# TK105_Hodetelefonforsterker.net
KiCad netlist of a schematic drawn in Altium Designer
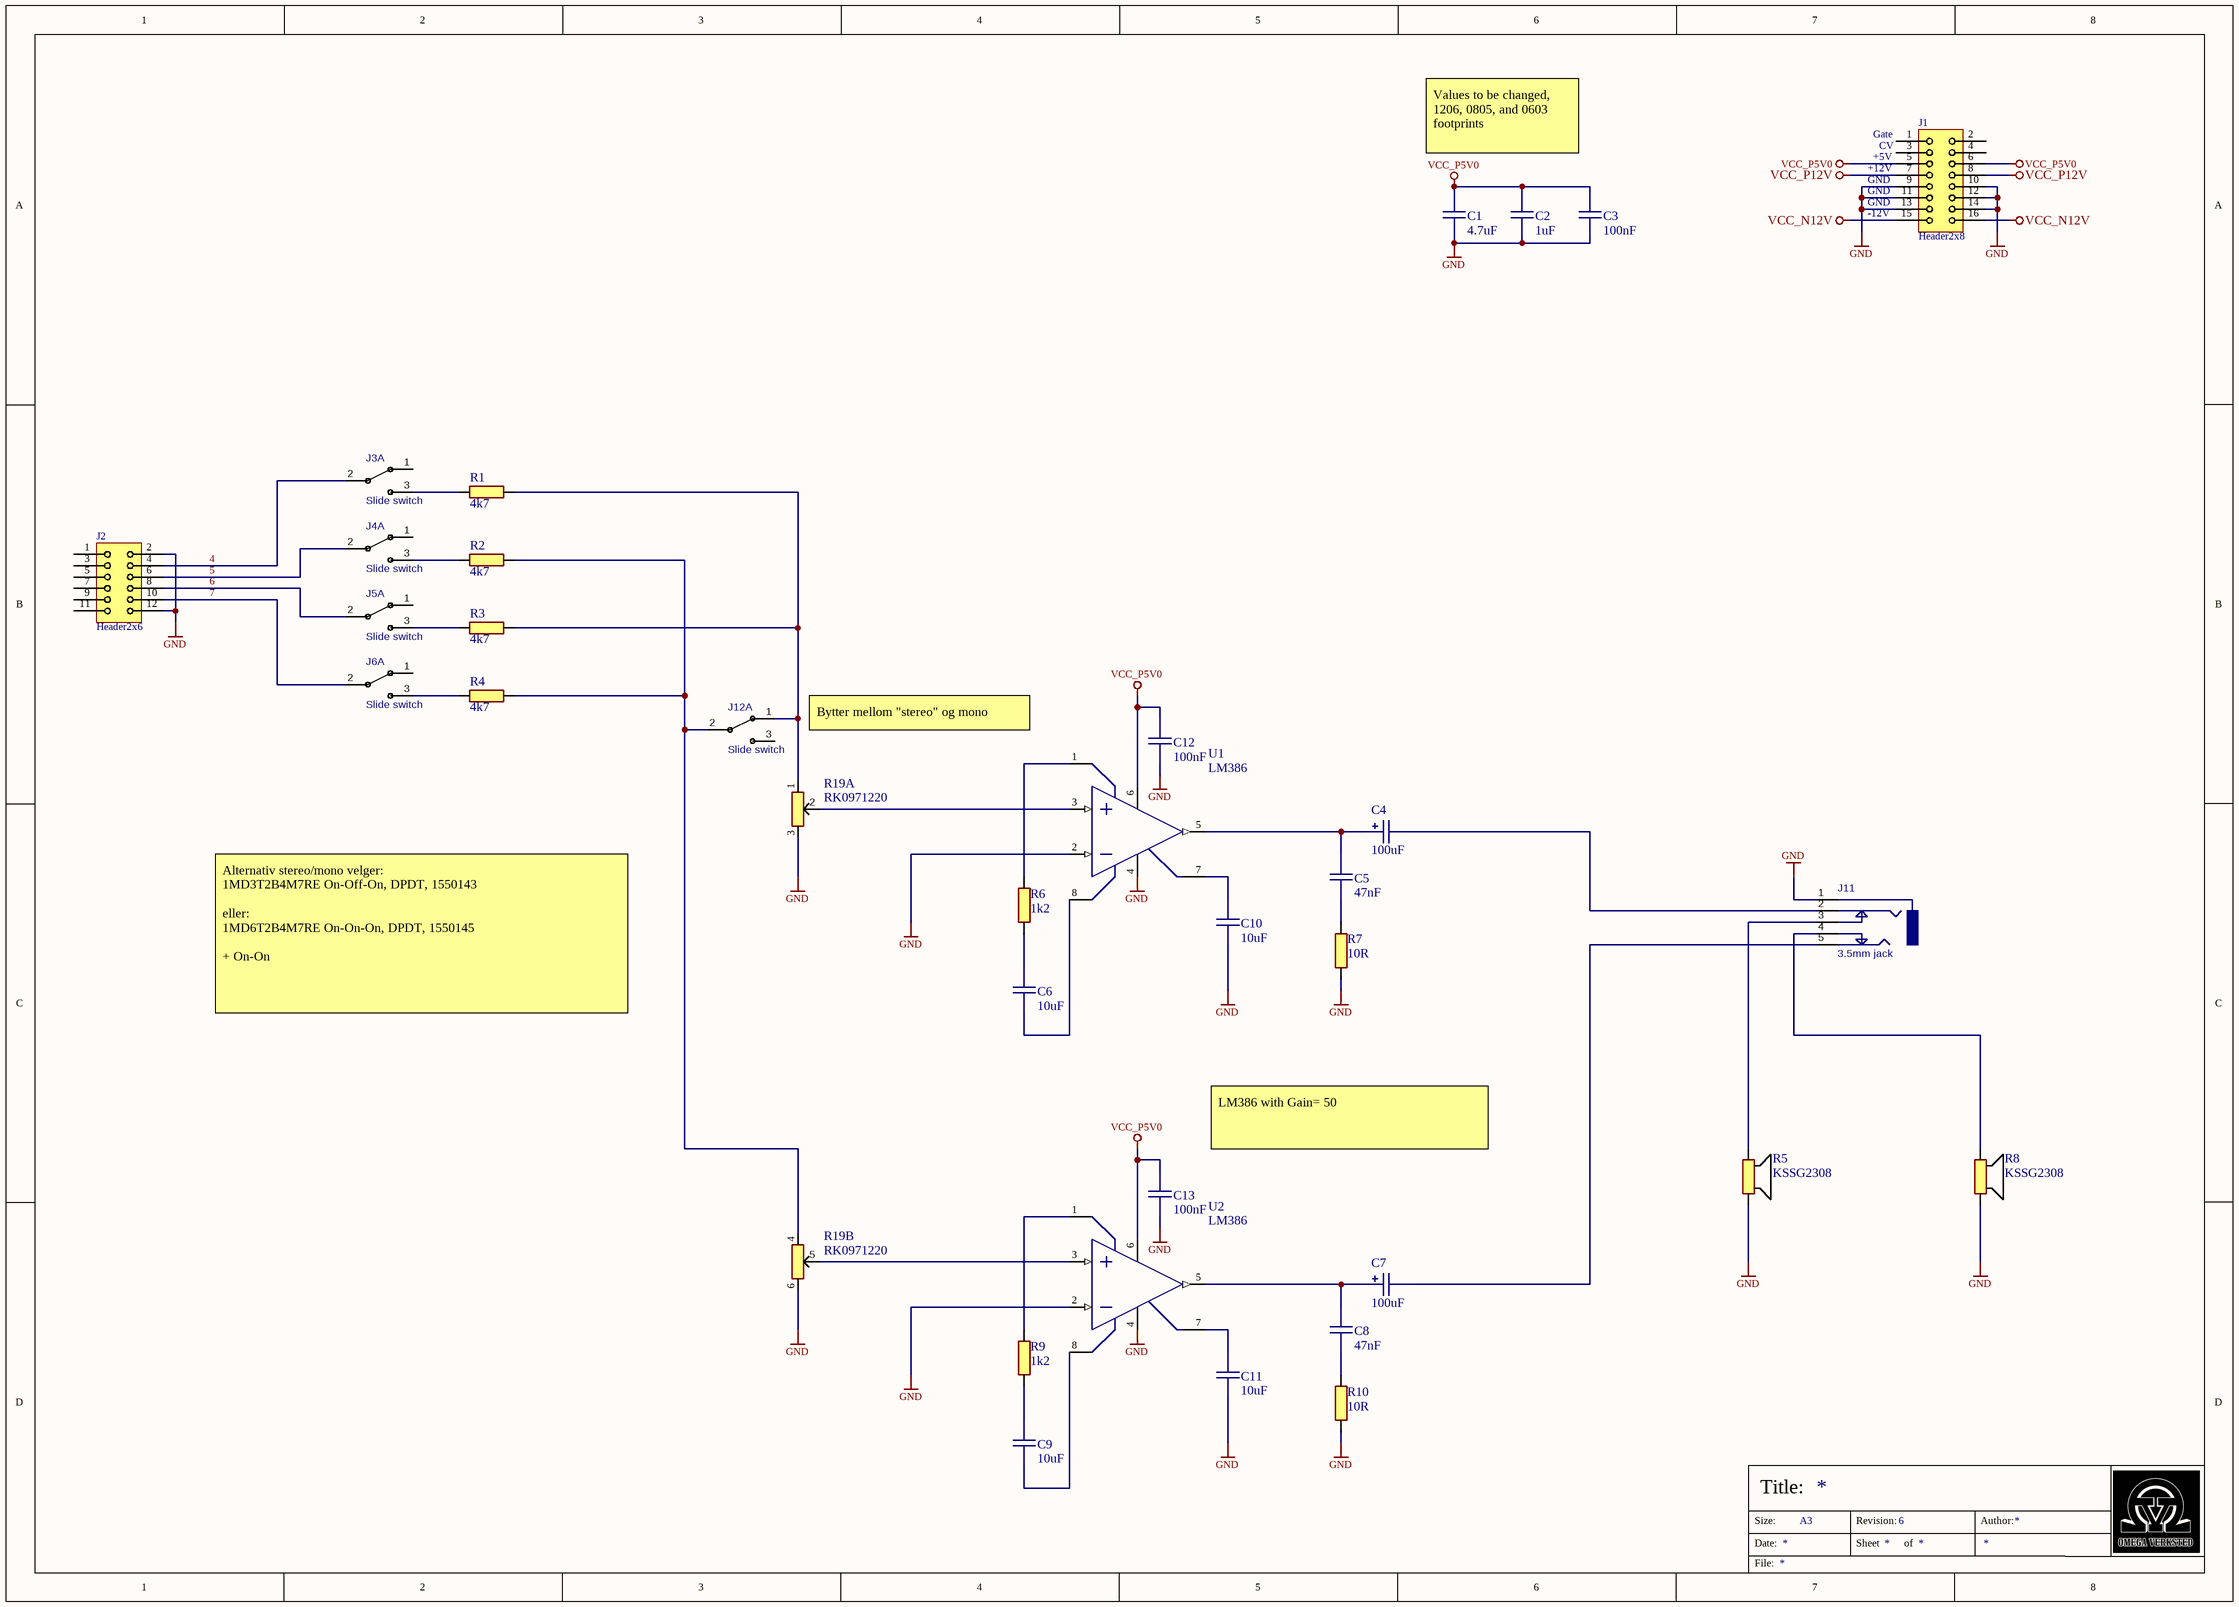
[diagram p0: TK105_Hodetelefonforsterker.SchDoc]

(export (version "E")
  (design (tool "Eeschema 10.0.6"))
  (components
    (comp (ref "C1")
      (value "4.7uF")
      (footprint "CAPC1206(3216)170_N")
      (description "X7R 50V")
      (libsource (lib "OVLib") (part "CAP"))
    )
    (comp (ref "C2")
      (value "1uF")
      (footprint "CAPC0805(2012)100_N")
      (description "X7R 50V 10%")
      (libsource (lib "OVLib") (part "CAP"))
    )
    (comp (ref "C3")
      (value "100nF")
      (footprint "CAPC0603(1608)55_N")
      (description "X7R 50V 5%")
      (libsource (lib "OVLib") (part "CAP"))
    )
    (comp (ref "C4")
      (value "100uF")
      (footprint "CAPPR25D06H11")
      (description "25V 2.5mm pitch")
      (libsource (lib "OVLib_64") (part "POLCAP"))
    )
    (comp (ref "C5")
      (value "47nF")
      (footprint "CAPC0603(1608)55_N")
      (description "X7R 50V 5%")
      (libsource (lib "OVLib_64") (part "CAP"))
    )
    (comp (ref "C6")
      (value "10uF")
      (footprint "CAPC0805(2012)100_N")
      (description "X5R 6.3V 10%")
      (libsource (lib "OVLib_64") (part "CAP"))
    )
    (comp (ref "C7")
      (value "100uF")
      (footprint "CAPPR25D06H11")
      (description "25V 2.5mm pitch")
      (libsource (lib "OVLib_64") (part "POLCAP"))
    )
    (comp (ref "C8")
      (value "47nF")
      (footprint "CAPC0603(1608)55_N")
      (description "X7R 50V 5%")
      (libsource (lib "OVLib_64") (part "CAP"))
    )
    (comp (ref "C9")
      (value "10uF")
      (footprint "CAPC0805(2012)100_N")
      (description "X5R 6.3V 10%")
      (libsource (lib "OVLib_64") (part "CAP"))
    )
    (comp (ref "C10")
      (value "10uF")
      (footprint "CAPC0805(2012)100_N")
      (description "X5R 6.3V 10%")
      (libsource (lib "OVLib_64") (part "CAP"))
    )
    (comp (ref "C11")
      (value "10uF")
      (footprint "CAPC0805(2012)100_N")
      (description "X5R 6.3V 10%")
      (libsource (lib "OVLib_64") (part "CAP"))
    )
    (comp (ref "C12")
      (value "100nF")
      (footprint "CAPC0603(1608)55_N")
      (description "X7R 50V 5%")
      (libsource (lib "OVLib_64") (part "CAP"))
    )
    (comp (ref "C13")
      (value "100nF")
      (footprint "CAPC0603(1608)55_N")
      (description "X7R 50V 5%")
      (libsource (lib "OVLib_64") (part "CAP"))
    )
    (comp (ref "J1")
      (value "Header2x8")
      (footprint "HDRV16W64P254_2X8_Shrouded")
      (libsource (lib "OVLib_64") (part "Header2x8"))
    )
    (comp (ref "J2")
      (value "Header2x6")
      (footprint "HDRV12W64P254_2X6_RA")
      (description "Header")
      (libsource (lib "OVLib_64") (part "Header2x6"))
    )
    (comp (ref "J3")
      (value "Slide switch")
      (footprint "1MS1T2B4M7RE")
      (description "Toggle Switch SPDT On-On")
      (libsource (lib "OVLib_64") (part "Slide_switch_DPDT_RA"))
    )
    (comp (ref "J4")
      (value "Slide switch")
      (footprint "1MS1T2B4M7RE")
      (description "Toggle Switch SPDT On-On")
      (libsource (lib "OVLib_64") (part "Slide_switch_DPDT_RA"))
    )
    (comp (ref "J5")
      (value "Slide switch")
      (footprint "1MS1T2B4M7RE")
      (description "Toggle Switch SPDT On-On")
      (libsource (lib "OVLib_64") (part "Slide_switch_DPDT_RA"))
    )
    (comp (ref "J6")
      (value "Slide switch")
      (footprint "1MS1T2B4M7RE")
      (description "Toggle Switch SPDT On-On")
      (libsource (lib "OVLib_64") (part "Slide_switch_DPDT_RA"))
    )
    (comp (ref "J11")
      (value "3.5mm jack")
      (footprint "PJ-306M")
      (description "PCB panel mount PJ-306M")
      (libsource (lib "OVLib_64") (part "3.5MM_JACK"))
    )
    (comp (ref "J12")
      (value "Slide switch")
      (footprint "1MS1T2B4M7RE")
      (description "Toggle Switch SPDT On-On")
      (libsource (lib "OVLib_64") (part "Slide_switch_DPDT_RA"))
    )
    (comp (ref "R1")
      (value "4k7")
      (footprint "RESC0603(1608)_N")
      (description "0.1W 1% Thick film resistor")
      (libsource (lib "") (part "Resistor2_1"))
    )
    (comp (ref "R2")
      (value "4k7")
      (footprint "RESC0603(1608)_N")
      (description "0.1W 1% Thick film resistor")
      (libsource (lib "") (part "Resistor2_1"))
    )
    (comp (ref "R3")
      (value "4k7")
      (footprint "RESC0603(1608)_N")
      (description "0.1W 1% Thick film resistor")
      (libsource (lib "") (part "Resistor2_1"))
    )
    (comp (ref "R4")
      (value "4k7")
      (footprint "RESC0603(1608)_N")
      (description "0.1W 1% Thick film resistor")
      (libsource (lib "") (part "Resistor2_1"))
    )
    (comp (ref "R5")
      (value "KSSG2308")
      (footprint "KSSG2308")
      (description "Speaker, Micro, 150 mW, 8 ohm, 1.5 kHz to 6 kHz")
      (libsource (lib "OVLib_64") (part "Speaker"))
    )
    (comp (ref "R6")
      (value "1k2")
      (footprint "RESC0603(1608)_N")
      (description "0.1W 1% Thick film resistor")
      (libsource (lib "OVLib_64") (part "Resistor2"))
    )
    (comp (ref "R7")
      (value "10R")
      (footprint "RESC0603(1608)_N")
      (description "0.1W 1% Thick film resistor")
      (libsource (lib "OVLib_64") (part "Resistor2"))
    )
    (comp (ref "R8")
      (value "KSSG2308")
      (footprint "KSSG2308")
      (description "Speaker, Micro, 150 mW, 8 ohm, 1.5 kHz to 6 kHz")
      (libsource (lib "OVLib_64") (part "Speaker"))
    )
    (comp (ref "R9")
      (value "1k2")
      (footprint "RESC0603(1608)_N")
      (description "0.1W 1% Thick film resistor")
      (libsource (lib "OVLib_64") (part "Resistor2"))
    )
    (comp (ref "R10")
      (value "10R")
      (footprint "RESC0603(1608)_N")
      (description "0.1W 1% Thick film resistor")
      (libsource (lib "OVLib_64") (part "Resistor2"))
    )
    (comp (ref "R19")
      (value "RK0971220")
      (footprint "RK0971220")
      (description "Stereo logarithmic potmeter")
      (libsource (lib "OVLib_64") (part "Stereo_Potmeter"))
    )
    (comp (ref "U1")
      (value "LM386")
      (footprint "SOIC127P590X363-8N")
      (description "Audio Power Amplifier, AB, 1 Channel, 4V to 12V, MSOP, 8 Pins")
      (libsource (lib "OVLib_64") (part "LM386"))
    )
    (comp (ref "U2")
      (value "LM386")
      (footprint "SOIC127P590X363-8N")
      (description "Audio Power Amplifier, AB, 1 Channel, 4V to 12V, MSOP, 8 Pins")
      (libsource (lib "OVLib_64") (part "LM386"))
    )
  )
  (nets
    (net (code "1") (name "/4") (class "Default")
      (node (ref "J2") (pin "4") (pinfunction "4_4") (pintype "passive"))
      (node (ref "J3") (pin "2") (pinfunction "2_2") (pintype "passive"))
    )
    (net (code "2") (name "/5") (class "Default")
      (node (ref "J2") (pin "6") (pinfunction "6_6") (pintype "passive"))
      (node (ref "J4") (pin "2") (pinfunction "2_2") (pintype "passive"))
    )
    (net (code "3") (name "/6") (class "Default")
      (node (ref "J2") (pin "8") (pinfunction "8_8") (pintype "passive"))
      (node (ref "J5") (pin "2") (pinfunction "2_2") (pintype "passive"))
    )
    (net (code "4") (name "/7") (class "Default")
      (node (ref "J2") (pin "10") (pinfunction "10_10") (pintype "passive"))
      (node (ref "J6") (pin "2") (pinfunction "2_2") (pintype "passive"))
    )
    (net (code "5") (name "GND") (class "Default")
      (node (ref "C1") (pin "1") (pinfunction "1_1") (pintype "passive"))
      (node (ref "C10") (pin "1") (pinfunction "1_1") (pintype "passive"))
      (node (ref "C11") (pin "1") (pinfunction "1_1") (pintype "passive"))
      (node (ref "C12") (pin "1") (pinfunction "1_1") (pintype "passive"))
      (node (ref "C13") (pin "1") (pinfunction "1_1") (pintype "passive"))
      (node (ref "C2") (pin "1") (pinfunction "1_1") (pintype "passive"))
      (node (ref "C3") (pin "1") (pinfunction "1_1") (pintype "passive"))
      (node (ref "J1") (pin "10") (pinfunction "10_10") (pintype "passive"))
      (node (ref "J1") (pin "11") (pinfunction "11_11") (pintype "passive"))
      (node (ref "J1") (pin "12") (pinfunction "12_12") (pintype "passive"))
      (node (ref "J1") (pin "13") (pinfunction "13_13") (pintype "passive"))
      (node (ref "J1") (pin "14") (pinfunction "14_14") (pintype "passive"))
      (node (ref "J1") (pin "9") (pinfunction "9_9") (pintype "passive"))
      (node (ref "J11") (pin "1") (pinfunction "1_1") (pintype "passive"))
      (node (ref "J2") (pin "12") (pinfunction "12_12") (pintype "passive"))
      (node (ref "J2") (pin "2") (pinfunction "2_2") (pintype "passive"))
      (node (ref "R10") (pin "1") (pinfunction "1_1") (pintype "passive"))
      (node (ref "R19") (pin "3") (pinfunction "3_3") (pintype "passive"))
      (node (ref "R19") (pin "6") (pinfunction "6_6") (pintype "passive"))
      (node (ref "R5") (pin "2") (pinfunction "2_2") (pintype "passive"))
      (node (ref "R7") (pin "1") (pinfunction "1_1") (pintype "passive"))
      (node (ref "R8") (pin "2") (pinfunction "2_2") (pintype "passive"))
      (node (ref "U1") (pin "2") (pinfunction "IN-_2") (pintype "input"))
      (node (ref "U1") (pin "4") (pinfunction "GND_4") (pintype "power_in"))
      (node (ref "U2") (pin "2") (pinfunction "IN-_2") (pintype "input"))
      (node (ref "U2") (pin "4") (pinfunction "GND_4") (pintype "power_in"))
    )
    (net (code "6") (name "Net-(C4-Pad1)") (class "Default")
      (node (ref "C4") (pin "1") (pinfunction "1_1") (pintype "passive"))
      (node (ref "J11") (pin "2") (pinfunction "2_2") (pintype "passive"))
    )
    (net (code "7") (name "Net-(C5-Pad1)") (class "Default")
      (node (ref "C5") (pin "1") (pinfunction "1_1") (pintype "passive"))
      (node (ref "R7") (pin "2") (pinfunction "2_2") (pintype "passive"))
    )
    (net (code "8") (name "Net-(C6-Pad1)") (class "Default")
      (node (ref "C6") (pin "1") (pinfunction "1_1") (pintype "passive"))
      (node (ref "U1") (pin "8") (pinfunction "GAIN_8") (pintype "passive"))
    )
    (net (code "9") (name "Net-(C6-Pad2)") (class "Default")
      (node (ref "C6") (pin "2") (pinfunction "2_2") (pintype "passive"))
      (node (ref "R6") (pin "1") (pinfunction "1_1") (pintype "passive"))
    )
    (net (code "10") (name "Net-(C7-Pad1)") (class "Default")
      (node (ref "C7") (pin "1") (pinfunction "1_1") (pintype "passive"))
      (node (ref "J11") (pin "5") (pinfunction "5_5") (pintype "passive"))
    )
    (net (code "11") (name "Net-(C8-Pad1)") (class "Default")
      (node (ref "C8") (pin "1") (pinfunction "1_1") (pintype "passive"))
      (node (ref "R10") (pin "2") (pinfunction "2_2") (pintype "passive"))
    )
    (net (code "12") (name "Net-(C9-Pad1)") (class "Default")
      (node (ref "C9") (pin "1") (pinfunction "1_1") (pintype "passive"))
      (node (ref "U2") (pin "8") (pinfunction "GAIN_8") (pintype "passive"))
    )
    (net (code "13") (name "Net-(C9-Pad2)") (class "Default")
      (node (ref "C9") (pin "2") (pinfunction "2_2") (pintype "passive"))
      (node (ref "R9") (pin "1") (pinfunction "1_1") (pintype "passive"))
    )
    (net (code "14") (name "Net-(J3-Pad3)") (class "Default")
      (node (ref "J3") (pin "3") (pinfunction "3_3") (pintype "passive"))
      (node (ref "R1") (pin "1") (pinfunction "1_1") (pintype "passive"))
    )
    (net (code "15") (name "Net-(J4-Pad3)") (class "Default")
      (node (ref "J4") (pin "3") (pinfunction "3_3") (pintype "passive"))
      (node (ref "R2") (pin "1") (pinfunction "1_1") (pintype "passive"))
    )
    (net (code "16") (name "Net-(J5-Pad3)") (class "Default")
      (node (ref "J5") (pin "3") (pinfunction "3_3") (pintype "passive"))
      (node (ref "R3") (pin "1") (pinfunction "1_1") (pintype "passive"))
    )
    (net (code "17") (name "Net-(J6-Pad3)") (class "Default")
      (node (ref "J6") (pin "3") (pinfunction "3_3") (pintype "passive"))
      (node (ref "R4") (pin "1") (pinfunction "1_1") (pintype "passive"))
    )
    (net (code "18") (name "Net-(J11-Pad3)") (class "Default")
      (node (ref "J11") (pin "3") (pinfunction "3_3") (pintype "passive"))
      (node (ref "R5") (pin "1") (pinfunction "1_1") (pintype "passive"))
    )
    (net (code "19") (name "Net-(J11-Pad4)") (class "Default")
      (node (ref "J11") (pin "4") (pinfunction "4_4") (pintype "passive"))
      (node (ref "R8") (pin "1") (pinfunction "1_1") (pintype "passive"))
    )
    (net (code "20") (name "Net-(J12-Pad1)") (class "Default")
      (node (ref "J12") (pin "1") (pinfunction "1_1") (pintype "passive"))
      (node (ref "R1") (pin "2") (pinfunction "2_2") (pintype "passive"))
      (node (ref "R19") (pin "1") (pinfunction "1_1") (pintype "passive"))
      (node (ref "R3") (pin "2") (pinfunction "2_2") (pintype "passive"))
    )
    (net (code "21") (name "Net-(J12-Pad2)") (class "Default")
      (node (ref "J12") (pin "2") (pinfunction "2_2") (pintype "passive"))
      (node (ref "R19") (pin "4") (pinfunction "4_4") (pintype "passive"))
      (node (ref "R2") (pin "2") (pinfunction "2_2") (pintype "passive"))
      (node (ref "R4") (pin "2") (pinfunction "2_2") (pintype "passive"))
    )
    (net (code "22") (name "Net-(R6-Pad2)") (class "Default")
      (node (ref "R6") (pin "2") (pinfunction "2_2") (pintype "passive"))
      (node (ref "U1") (pin "1") (pinfunction "GAIN_1") (pintype "power_in"))
    )
    (net (code "23") (name "Net-(R9-Pad2)") (class "Default")
      (node (ref "R9") (pin "2") (pinfunction "2_2") (pintype "passive"))
      (node (ref "U2") (pin "1") (pinfunction "GAIN_1") (pintype "power_in"))
    )
    (net (code "24") (name "Net-(U1-BYPASS)") (class "Default")
      (node (ref "C10") (pin "2") (pinfunction "2_2") (pintype "passive"))
      (node (ref "U1") (pin "7") (pinfunction "BYPASS_7") (pintype "passive"))
    )
    (net (code "25") (name "Net-(U1-IN+)") (class "Default")
      (node (ref "R19") (pin "2") (pinfunction "2_2") (pintype "passive"))
      (node (ref "U1") (pin "3") (pinfunction "IN+_3") (pintype "input"))
    )
    (net (code "26") (name "Net-(U1-OUT)") (class "Default")
      (node (ref "C4") (pin "2") (pinfunction "2_2") (pintype "passive"))
      (node (ref "C5") (pin "2") (pinfunction "2_2") (pintype "passive"))
      (node (ref "U1") (pin "5") (pinfunction "OUT_5") (pintype "output"))
    )
    (net (code "27") (name "Net-(U2-BYPASS)") (class "Default")
      (node (ref "C11") (pin "2") (pinfunction "2_2") (pintype "passive"))
      (node (ref "U2") (pin "7") (pinfunction "BYPASS_7") (pintype "passive"))
    )
    (net (code "28") (name "Net-(U2-IN+)") (class "Default")
      (node (ref "R19") (pin "5") (pinfunction "5_5") (pintype "passive"))
      (node (ref "U2") (pin "3") (pinfunction "IN+_3") (pintype "input"))
    )
    (net (code "29") (name "Net-(U2-OUT)") (class "Default")
      (node (ref "C7") (pin "2") (pinfunction "2_2") (pintype "passive"))
      (node (ref "C8") (pin "2") (pinfunction "2_2") (pintype "passive"))
      (node (ref "U2") (pin "5") (pinfunction "OUT_5") (pintype "output"))
    )
    (net (code "30") (name "VCC_N12V") (class "Default")
      (node (ref "J1") (pin "15") (pinfunction "15_15") (pintype "passive"))
      (node (ref "J1") (pin "16") (pinfunction "16_16") (pintype "passive"))
    )
    (net (code "31") (name "VCC_P5V0") (class "Default")
      (node (ref "C1") (pin "2") (pinfunction "2_2") (pintype "passive"))
      (node (ref "C12") (pin "2") (pinfunction "2_2") (pintype "passive"))
      (node (ref "C13") (pin "2") (pinfunction "2_2") (pintype "passive"))
      (node (ref "C2") (pin "2") (pinfunction "2_2") (pintype "passive"))
      (node (ref "C3") (pin "2") (pinfunction "2_2") (pintype "passive"))
      (node (ref "J1") (pin "5") (pinfunction "5_5") (pintype "passive"))
      (node (ref "J1") (pin "6") (pinfunction "6_6") (pintype "passive"))
      (node (ref "U1") (pin "6") (pinfunction "Vs_6") (pintype "power_in"))
      (node (ref "U2") (pin "6") (pinfunction "Vs_6") (pintype "power_in"))
    )
    (net (code "32") (name "VCC_P12V") (class "Default")
      (node (ref "J1") (pin "7") (pinfunction "7_7") (pintype "passive"))
      (node (ref "J1") (pin "8") (pinfunction "8_8") (pintype "passive"))
    )
    (net (code "33") (name "unconnected-(J1-Pad1)") (class "Default")
      (node (ref "J1") (pin "1") (pinfunction "1_1") (pintype "passive"))
    )
    (net (code "34") (name "unconnected-(J1-Pad2)") (class "Default")
      (node (ref "J1") (pin "2") (pinfunction "2_2") (pintype "passive"))
    )
    (net (code "35") (name "unconnected-(J1-Pad3)") (class "Default")
      (node (ref "J1") (pin "3") (pinfunction "3_3") (pintype "passive"))
    )
    (net (code "36") (name "unconnected-(J1-Pad4)") (class "Default")
      (node (ref "J1") (pin "4") (pinfunction "4_4") (pintype "passive"))
    )
    (net (code "37") (name "unconnected-(J2-Pad1)") (class "Default")
      (node (ref "J2") (pin "1") (pinfunction "1_1") (pintype "passive"))
    )
    (net (code "38") (name "unconnected-(J2-Pad3)") (class "Default")
      (node (ref "J2") (pin "3") (pinfunction "3_3") (pintype "passive"))
    )
    (net (code "39") (name "unconnected-(J2-Pad5)") (class "Default")
      (node (ref "J2") (pin "5") (pinfunction "5_5") (pintype "passive"))
    )
    (net (code "40") (name "unconnected-(J2-Pad7)") (class "Default")
      (node (ref "J2") (pin "7") (pinfunction "7_7") (pintype "passive"))
    )
    (net (code "41") (name "unconnected-(J2-Pad9)") (class "Default")
      (node (ref "J2") (pin "9") (pinfunction "9_9") (pintype "passive"))
    )
    (net (code "42") (name "unconnected-(J2-Pad11)") (class "Default")
      (node (ref "J2") (pin "11") (pinfunction "11_11") (pintype "passive"))
    )
    (net (code "43") (name "unconnected-(J3-Pad1)") (class "Default")
      (node (ref "J3") (pin "1") (pinfunction "1_1") (pintype "passive"))
    )
    (net (code "44") (name "unconnected-(J4-Pad1)") (class "Default")
      (node (ref "J4") (pin "1") (pinfunction "1_1") (pintype "passive"))
    )
    (net (code "45") (name "unconnected-(J5-Pad1)") (class "Default")
      (node (ref "J5") (pin "1") (pinfunction "1_1") (pintype "passive"))
    )
    (net (code "46") (name "unconnected-(J6-Pad1)") (class "Default")
      (node (ref "J6") (pin "1") (pinfunction "1_1") (pintype "passive"))
    )
    (net (code "47") (name "unconnected-(J12-Pad3)") (class "Default")
      (node (ref "J12") (pin "3") (pinfunction "3_3") (pintype "passive"))
    )
  )
)
